# ENC.net
KiCad netlist of a schematic drawn in EAGLE
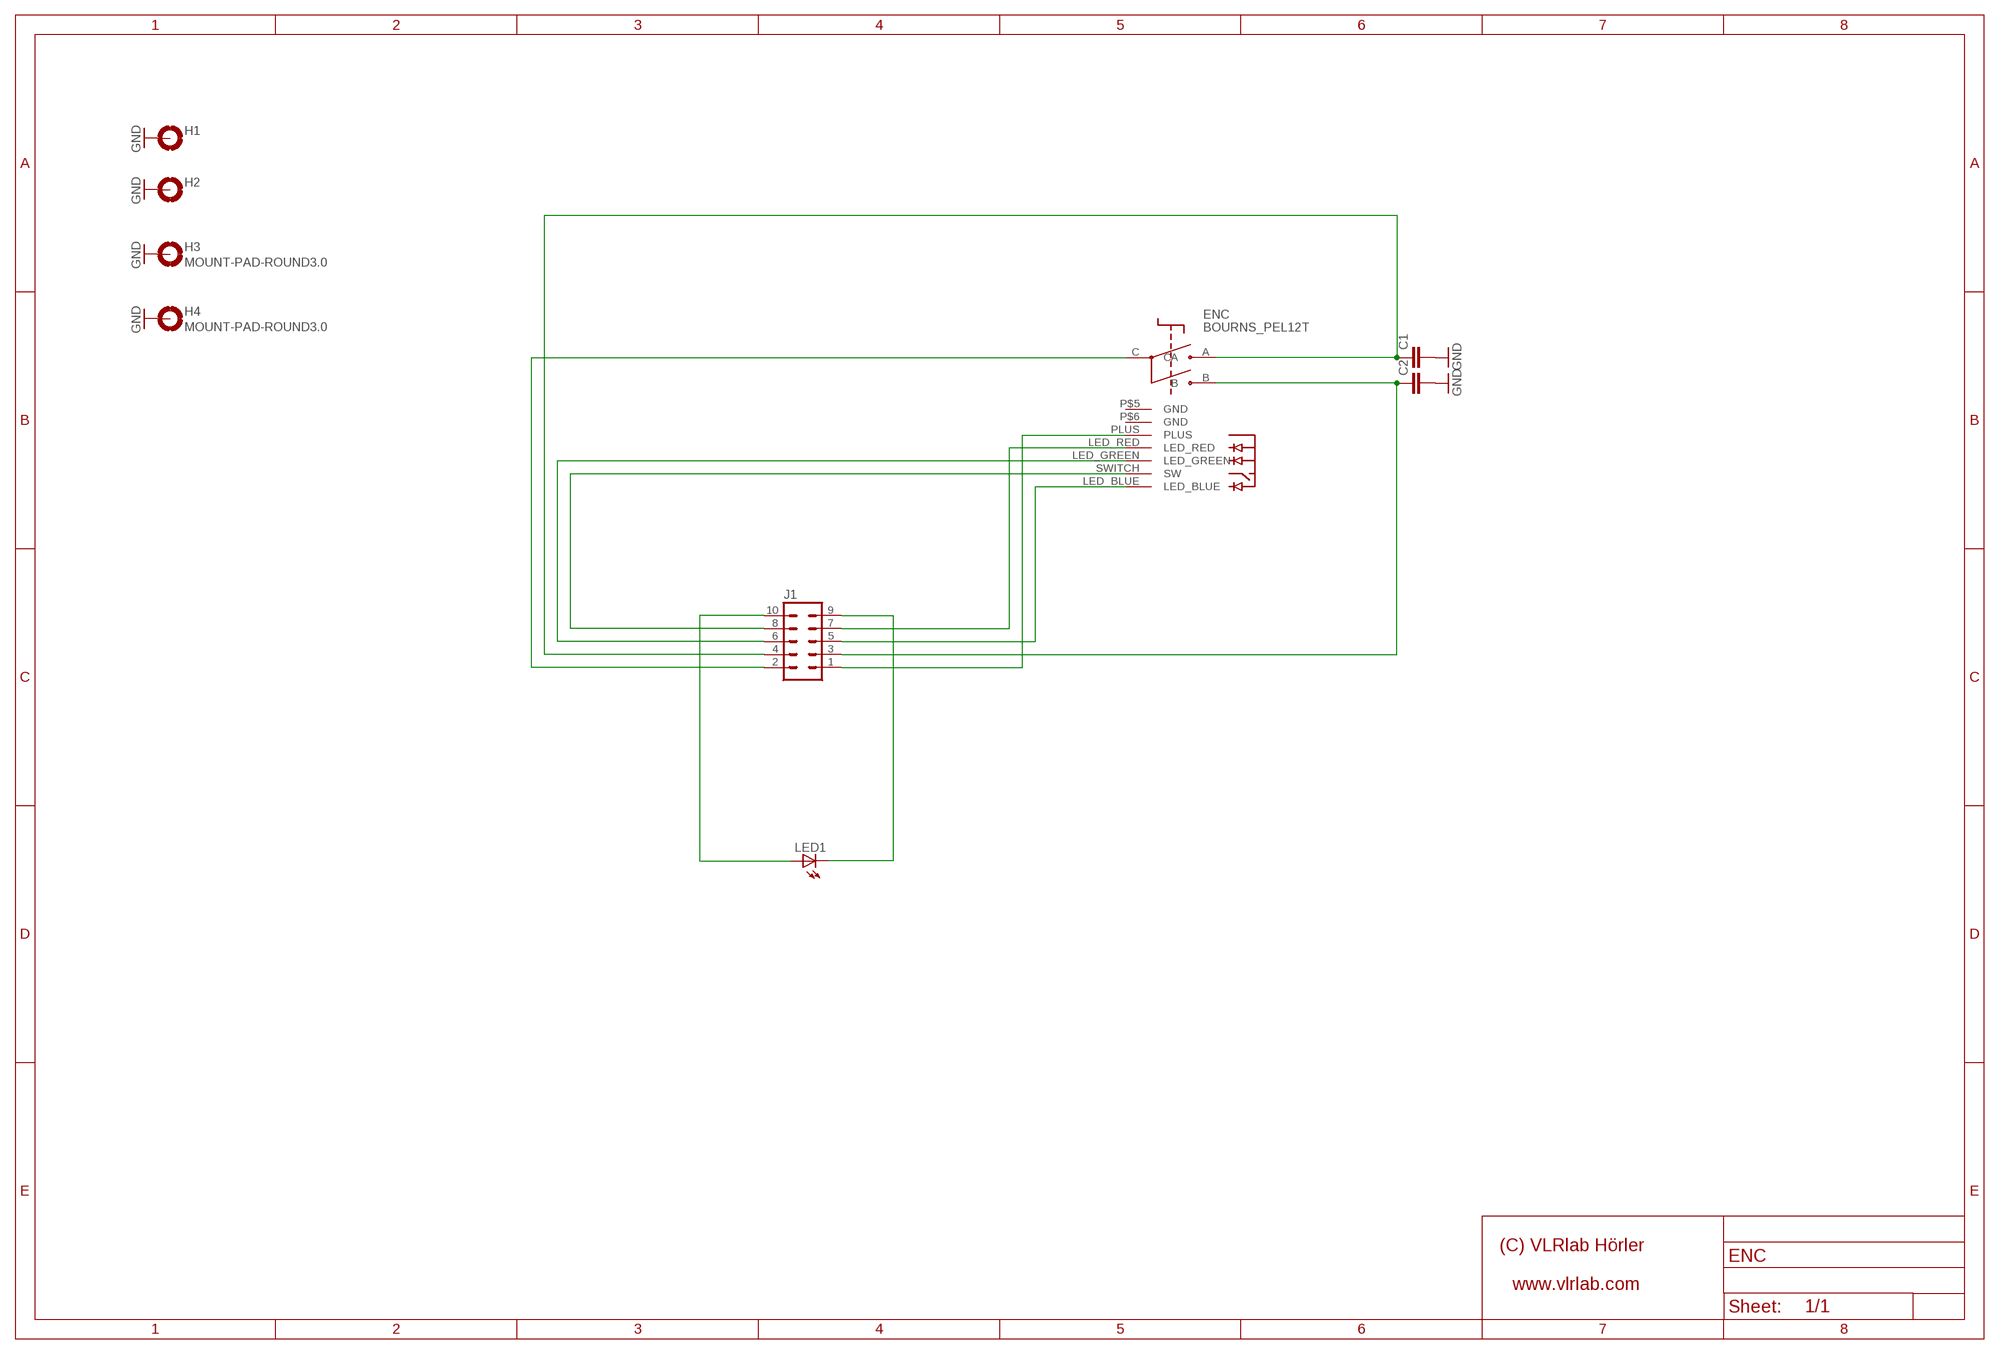
[diagram p0: schematic, sheet 1]

(export (version "E")
  (design (tool "Eeschema 10.0.6"))
  (components
    (comp (ref "C1")
      (value "C-EU025-025X050")
      (footprint "eagle-import:C025-025X050")
      (libsource (lib "eagle-import") (part "C-EU025-025X050"))
    )
    (comp (ref "C2")
      (value "C-EU025-025X050")
      (footprint "eagle-import:C025-025X050")
      (libsource (lib "eagle-import") (part "C-EU025-025X050"))
    )
    (comp (ref "ENC")
      (value "BOURNS_PEL12T")
      (footprint "eagle-import:PEL12T")
      (libsource (lib "eagle-import") (part "BOURNS_PEL12T"))
    )
    (comp (ref "H1")
      (value "MOUNT-PAD-ROUND3.0")
      (footprint "eagle-import:3,0-PAD")
      (libsource (lib "eagle-import") (part "MOUNT-PAD-ROUND3.0"))
    )
    (comp (ref "H2")
      (value "MOUNT-PAD-ROUND3.0")
      (footprint "eagle-import:3,0-PAD")
      (libsource (lib "eagle-import") (part "MOUNT-PAD-ROUND3.0"))
    )
    (comp (ref "H3")
      (value "MOUNT-PAD-ROUND3.0")
      (footprint "eagle-import:3,0-PAD")
      (libsource (lib "eagle-import") (part "MOUNT-PAD-ROUND3.0"))
    )
    (comp (ref "H4")
      (value "MOUNT-PAD-ROUND3.0")
      (footprint "eagle-import:3,0-PAD")
      (libsource (lib "eagle-import") (part "MOUNT-PAD-ROUND3.0"))
    )
    (comp (ref "J1")
      (value "ML10ML10_TEXTFRONT")
      (footprint "eagle-import:ML10_TEXTFRONT")
      (libsource (lib "eagle-import") (part "ML10ML10_TEXTFRONT"))
    )
    (comp (ref "LED1")
      (value "LED3MM")
      (footprint "eagle-import:LED3MM")
      (libsource (lib "eagle-import") (part "LED3MM"))
    )
  )
  (nets
    (net (code "1") (name "GND") (class "Default")
      (node (ref "C1") (pin "2") (pinfunction "2_2") (pintype "passive"))
      (node (ref "C2") (pin "2") (pinfunction "2_2") (pintype "passive"))
      (node (ref "H1") (pin "B3,0") (pinfunction "MOUNT_B3,0") (pintype "passive"))
      (node (ref "H2") (pin "B3,0") (pinfunction "MOUNT_B3,0") (pintype "passive"))
      (node (ref "H3") (pin "B3,0") (pinfunction "MOUNT_B3,0") (pintype "passive"))
      (node (ref "H4") (pin "B3,0") (pinfunction "MOUNT_B3,0") (pintype "passive"))
    )
    (net (code "2") (name "Net-(C1-Pad1)") (class "Default")
      (node (ref "C1") (pin "1") (pinfunction "1_1") (pintype "passive"))
      (node (ref "ENC") (pin "A") (pinfunction "A_A") (pintype "bidirectional"))
      (node (ref "J1") (pin "4") (pinfunction "4_4") (pintype "passive"))
    )
    (net (code "3") (name "Net-(C2-Pad1)") (class "Default")
      (node (ref "C2") (pin "1") (pinfunction "1_1") (pintype "passive"))
      (node (ref "ENC") (pin "B") (pinfunction "B_B") (pintype "bidirectional"))
      (node (ref "J1") (pin "3") (pinfunction "3_3") (pintype "passive"))
    )
    (net (code "4") (name "Net-(ENC-PadC)") (class "Default")
      (node (ref "ENC") (pin "C") (pinfunction "C_C") (pintype "bidirectional"))
      (node (ref "J1") (pin "2") (pinfunction "2_2") (pintype "passive"))
    )
    (net (code "5") (name "Net-(ENC-PadLED_BLUE)") (class "Default")
      (node (ref "ENC") (pin "LED_BLUE") (pinfunction "LED_BLUE_LED_BLUE") (pintype "bidirectional"))
      (node (ref "J1") (pin "5") (pinfunction "5_5") (pintype "passive"))
    )
    (net (code "6") (name "Net-(ENC-PadLED_GREEN)") (class "Default")
      (node (ref "ENC") (pin "LED_GREEN") (pinfunction "LED_GREEN_LED_GREEN") (pintype "bidirectional"))
      (node (ref "J1") (pin "6") (pinfunction "6_6") (pintype "passive"))
    )
    (net (code "7") (name "Net-(ENC-PadLED_RED)") (class "Default")
      (node (ref "ENC") (pin "LED_RED") (pinfunction "LED_RED_LED_RED") (pintype "bidirectional"))
      (node (ref "J1") (pin "7") (pinfunction "7_7") (pintype "passive"))
    )
    (net (code "8") (name "Net-(ENC-PadPLUS)") (class "Default")
      (node (ref "ENC") (pin "PLUS") (pinfunction "PLUS_PLUS") (pintype "bidirectional"))
      (node (ref "J1") (pin "1") (pinfunction "1_1") (pintype "passive"))
    )
    (net (code "9") (name "Net-(ENC-SW)") (class "Default")
      (node (ref "ENC") (pin "SWITCH") (pinfunction "SW_SWITCH") (pintype "bidirectional"))
      (node (ref "J1") (pin "8") (pinfunction "8_8") (pintype "passive"))
    )
    (net (code "10") (name "Net-(J1-Pad10)") (class "Default")
      (node (ref "J1") (pin "10") (pinfunction "10_10") (pintype "passive"))
      (node (ref "LED1") (pin "A") (pinfunction "A_A") (pintype "passive"))
    )
    (net (code "11") (name "Net-(LED1-C)") (class "Default")
      (node (ref "J1") (pin "9") (pinfunction "9_9") (pintype "passive"))
      (node (ref "LED1") (pin "K") (pinfunction "C_K") (pintype "passive"))
    )
    (net (code "12") (name "unconnected-(ENC-GND-PadP$5)") (class "Default")
      (node (ref "ENC") (pin "P$5") (pinfunction "GND_P$5") (pintype "bidirectional"))
    )
    (net (code "13") (name "unconnected-(ENC-GND-PadP$6)") (class "Default")
      (node (ref "ENC") (pin "P$6") (pinfunction "GND_P$6") (pintype "bidirectional"))
    )
  )
)
